# AugmentedStethoscope_v2c.net
KiCad netlist of a schematic drawn in EAGLE
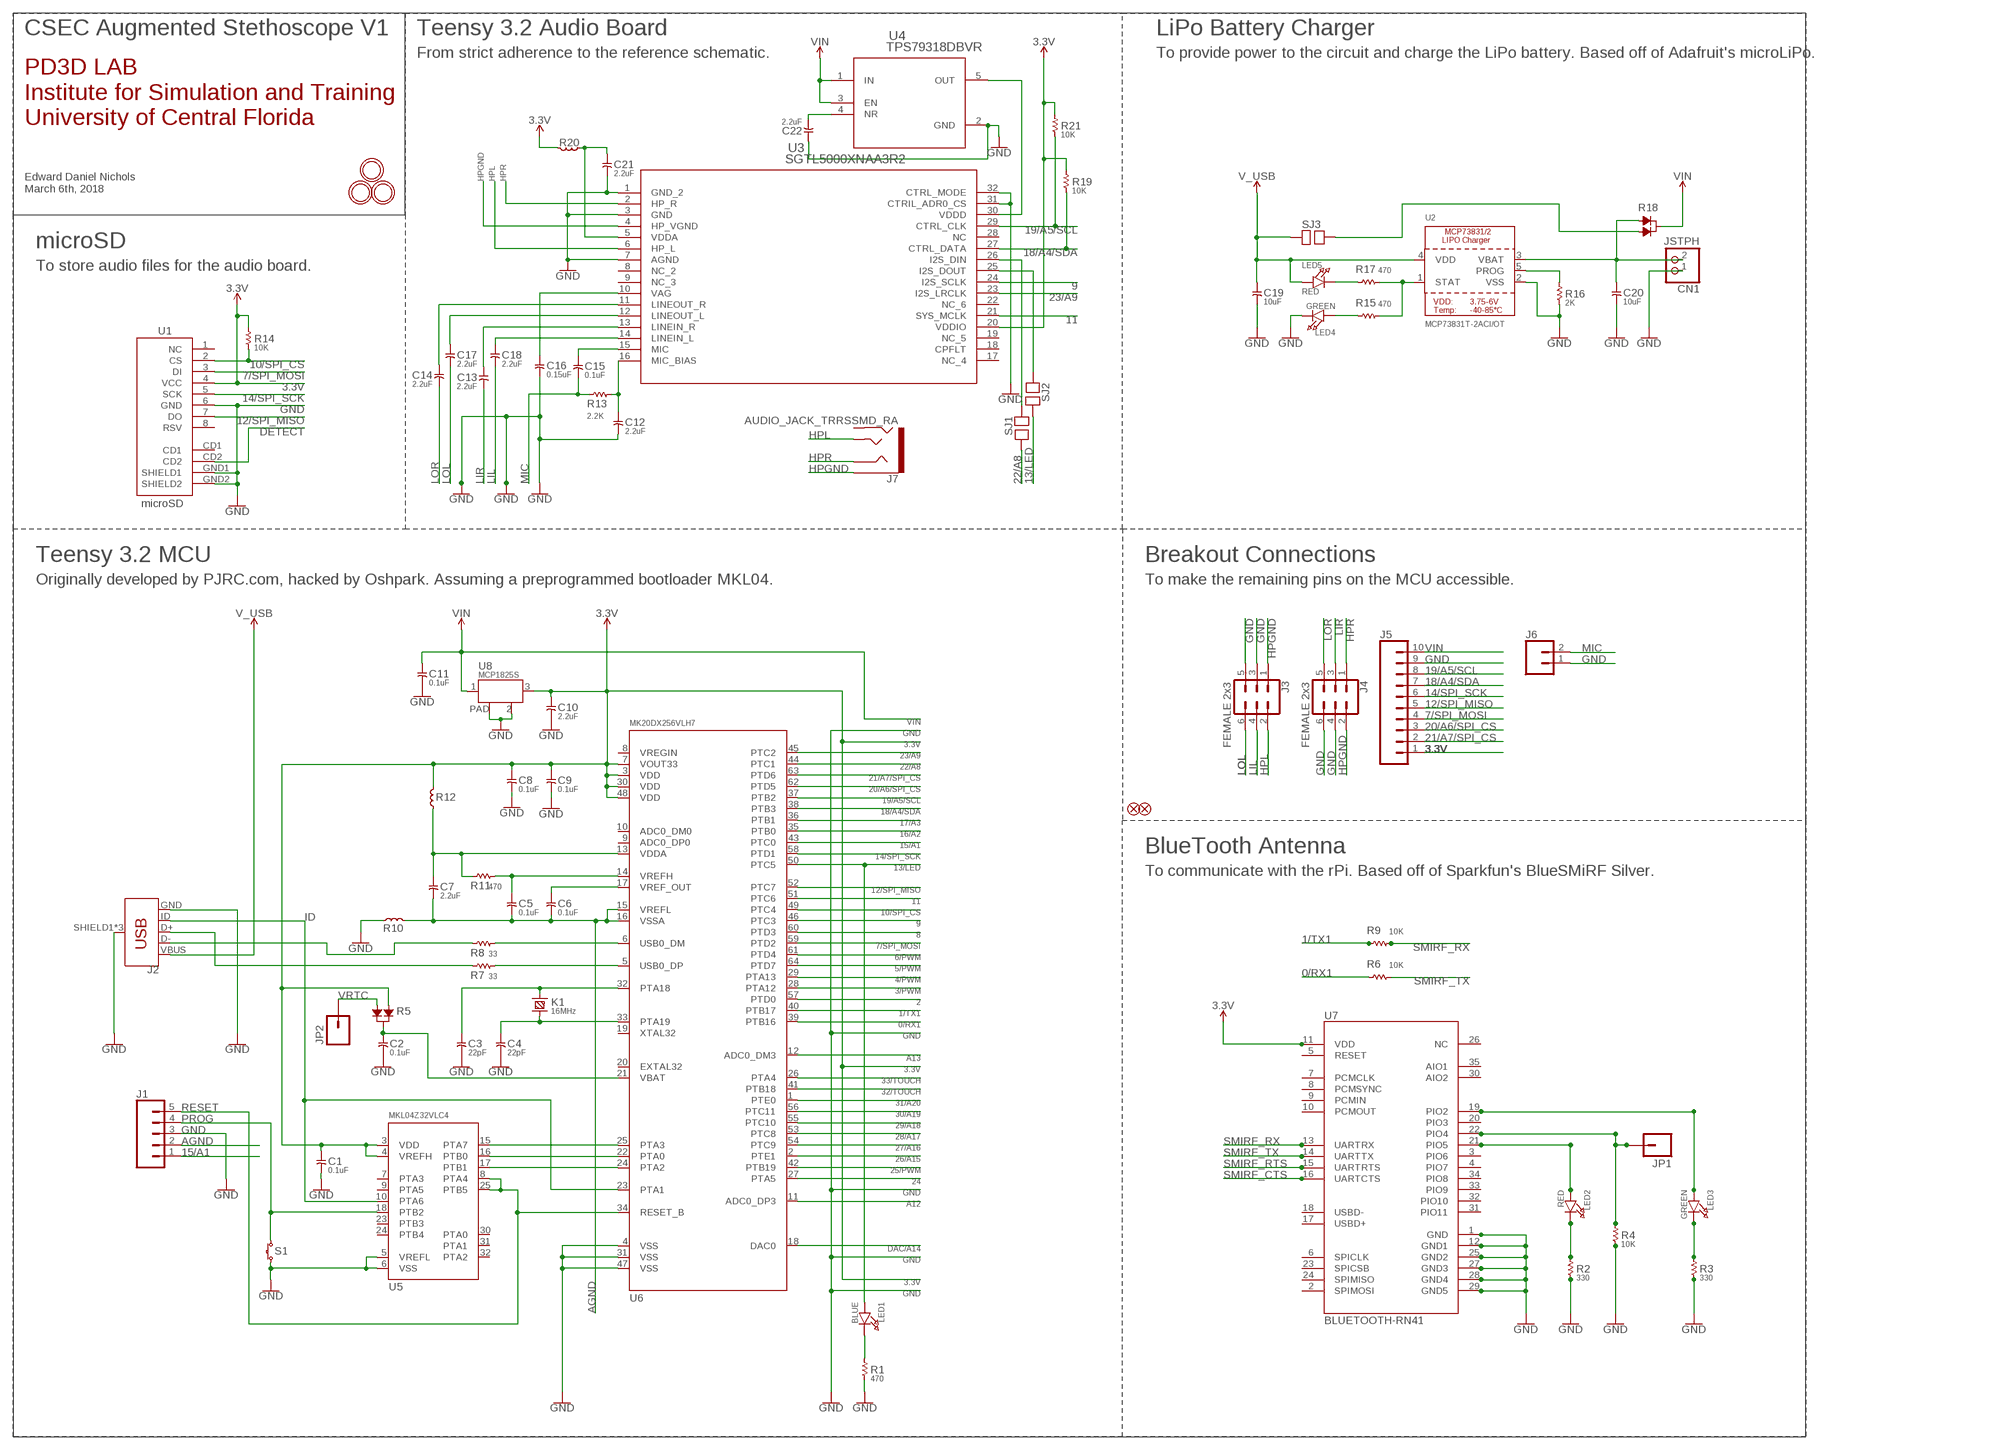
[diagram p0: schematic, sheet 1]

(export (version "E")
  (design (tool "Eeschema 10.0.6"))
  (components
    (comp (ref "C1")
      (value "0.1uF")
      (footprint "eagle-import:C0603")
      (fields (field (name "MF") "Murata Electronics") (field (name "MPN") "GRM188R71C104KA01D"))
      (libsource (lib "eagle-import") (part "CAPACITOR-0.1UF"))
    )
    (comp (ref "C2")
      (value "0.1uF")
      (footprint "eagle-import:C0603")
      (fields (field (name "MF") "Murata Electronics") (field (name "MPN") "GRM188R71C104KA01D"))
      (libsource (lib "eagle-import") (part "CAPACITOR-0.1UF"))
    )
    (comp (ref "C3")
      (value "22pF")
      (footprint "eagle-import:C0603")
      (fields (field (name "MF") "Vishay / Vitramon") (field (name "MPN") "VJ0603A220JXACW1BC"))
      (libsource (lib "eagle-import") (part "CAPACITOR-22PF"))
    )
    (comp (ref "C4")
      (value "22pF")
      (footprint "eagle-import:C0603")
      (fields (field (name "MF") "Vishay / Vitramon") (field (name "MPN") "VJ0603A220JXACW1BC"))
      (libsource (lib "eagle-import") (part "CAPACITOR-22PF"))
    )
    (comp (ref "C5")
      (value "0.1uF")
      (footprint "eagle-import:C0603")
      (fields (field (name "MF") "Murata Electronics") (field (name "MPN") "GRM188R71C104KA01D"))
      (libsource (lib "eagle-import") (part "CAPACITOR-0.1UF"))
    )
    (comp (ref "C6")
      (value "0.1uF")
      (footprint "eagle-import:C0603")
      (fields (field (name "MF") "Murata Electronics") (field (name "MPN") "GRM188R71C104KA01D"))
      (libsource (lib "eagle-import") (part "CAPACITOR-0.1UF"))
    )
    (comp (ref "C7")
      (value "2.2uF")
      (footprint "eagle-import:C0805")
      (fields (field (name "MF") "Taiyo Yuden") (field (name "MPN") "TMK212B7225KG-TR"))
      (libsource (lib "eagle-import") (part "CAPACITOR-2.2UF"))
    )
    (comp (ref "C8")
      (value "0.1uF")
      (footprint "eagle-import:C0603")
      (fields (field (name "MF") "Murata Electronics") (field (name "MPN") "GRM188R71C104KA01D"))
      (libsource (lib "eagle-import") (part "CAPACITOR-0.1UF"))
    )
    (comp (ref "C9")
      (value "0.1uF")
      (footprint "eagle-import:C0603")
      (fields (field (name "MF") "Murata Electronics") (field (name "MPN") "GRM188R71C104KA01D"))
      (libsource (lib "eagle-import") (part "CAPACITOR-0.1UF"))
    )
    (comp (ref "C10")
      (value "2.2uF")
      (footprint "eagle-import:C0805")
      (fields (field (name "MF") "Taiyo Yuden") (field (name "MPN") "TMK212B7225KG-TR"))
      (libsource (lib "eagle-import") (part "CAPACITOR-2.2UF"))
    )
    (comp (ref "C11")
      (value "0.1uF")
      (footprint "eagle-import:C0603")
      (fields (field (name "MF") "Murata Electronics") (field (name "MPN") "GRM188R71C104KA01D"))
      (libsource (lib "eagle-import") (part "CAPACITOR-0.1UF"))
    )
    (comp (ref "C12")
      (value "2.2uF")
      (footprint "eagle-import:C0805")
      (fields (field (name "MF") "Taiyo Yuden") (field (name "MPN") "TMK212B7225KG-TR"))
      (libsource (lib "eagle-import") (part "CAPACITOR-2.2UF"))
    )
    (comp (ref "C13")
      (value "2.2uF")
      (footprint "eagle-import:C0805")
      (fields (field (name "MF") "Taiyo Yuden") (field (name "MPN") "TMK212B7225KG-TR"))
      (libsource (lib "eagle-import") (part "CAPACITOR-2.2UF"))
    )
    (comp (ref "C14")
      (value "2.2uF")
      (footprint "eagle-import:C0805")
      (fields (field (name "MF") "Taiyo Yuden") (field (name "MPN") "TMK212B7225KG-TR"))
      (libsource (lib "eagle-import") (part "CAPACITOR-2.2UF"))
    )
    (comp (ref "C15")
      (value "0.1uF")
      (footprint "eagle-import:C0805")
      (fields (field (name "MF") "Taiyo Yuden") (field (name "MPN") "TMK212B7225KG-TR"))
      (libsource (lib "eagle-import") (part "CAPACITOR-2.2UF"))
    )
    (comp (ref "C16")
      (value "0.15uF")
      (footprint "eagle-import:C0603")
      (fields (field (name "MF") "Murata Electronics") (field (name "MPN") "GRM188R71C104KA01D"))
      (libsource (lib "eagle-import") (part "CAPACITOR-0.1UF"))
    )
    (comp (ref "C17")
      (value "2.2uF")
      (footprint "eagle-import:C0805")
      (fields (field (name "MF") "Taiyo Yuden") (field (name "MPN") "TMK212B7225KG-TR"))
      (libsource (lib "eagle-import") (part "CAPACITOR-2.2UF"))
    )
    (comp (ref "C18")
      (value "2.2uF")
      (footprint "eagle-import:C0805")
      (fields (field (name "MF") "Taiyo Yuden") (field (name "MPN") "TMK212B7225KG-TR"))
      (libsource (lib "eagle-import") (part "CAPACITOR-2.2UF"))
    )
    (comp (ref "C19")
      (value "10uF")
      (footprint "eagle-import:C0603")
      (fields (field (name "MF") "Murata Electronics") (field (name "MPN") "GRM188R71C104KA01D"))
      (libsource (lib "eagle-import") (part "CAPACITOR-0.1UF"))
    )
    (comp (ref "C20")
      (value "10uF")
      (footprint "eagle-import:C0603")
      (fields (field (name "MF") "Murata Electronics") (field (name "MPN") "GRM188R71C104KA01D"))
      (libsource (lib "eagle-import") (part "CAPACITOR-0.1UF"))
    )
    (comp (ref "C21")
      (value "2.2uF")
      (footprint "eagle-import:C0805")
      (fields (field (name "MF") "Taiyo Yuden") (field (name "MPN") "TMK212B7225KG-TR"))
      (libsource (lib "eagle-import") (part "CAPACITOR-2.2UF"))
    )
    (comp (ref "C22")
      (value "2.2uF")
      (footprint "eagle-import:C0805")
      (fields (field (name "MF") "Taiyo Yuden") (field (name "MPN") "TMK212B7225KG-TR"))
      (libsource (lib "eagle-import") (part "CAPACITOR-2.2UF"))
    )
    (comp (ref "CN1")
      (value "JSTPH")
      (footprint "eagle-import:JSTPH2")
      (libsource (lib "eagle-import") (part "JST_2PIN"))
    )
    (comp (ref "FID2")
      (value "FIDUCIAL\"\"")
      (footprint "eagle-import:FIDUCIAL_1MM")
      (libsource (lib "eagle-import") (part "FIDUCIAL{dblquote}{dblquote}"))
    )
    (comp (ref "FID3")
      (value "FIDUCIAL\"\"")
      (footprint "eagle-import:FIDUCIAL_1MM")
      (fields (field (name "BOM") "EXCLUDE"))
      (libsource (lib "eagle-import") (part "FIDUCIAL{dblquote}{dblquote}"))
    )
    (comp (ref "J1")
      (value "CONN_05")
      (footprint "eagle-import:1X05")
      (libsource (lib "eagle-import") (part "CONN_05"))
    )
    (comp (ref "J2")
      (value "USB_MICRO-B_FEMALE-SMT")
      (footprint "eagle-import:USB-B-MICRO-SMD")
      (libsource (lib "eagle-import") (part "USB_MICRO-B_FEMALE-SMT"))
    )
    (comp (ref "J3")
      (value "FEMALE 2x3")
      (footprint "eagle-import:2X3")
      (libsource (lib "eagle-import") (part "CONN_03X2FEMALE"))
    )
    (comp (ref "J4")
      (value "FEMALE 2x3")
      (footprint "eagle-import:2X3")
      (libsource (lib "eagle-import") (part "CONN_03X2FEMALE"))
    )
    (comp (ref "J5")
      (value "CONN_10\"")
      (footprint "eagle-import:1X10")
      (libsource (lib "eagle-import") (part "CONN_10{dblquote}"))
    )
    (comp (ref "J6")
      (value "CONN_02")
      (footprint "eagle-import:1X02")
      (libsource (lib "eagle-import") (part "CONN_02"))
    )
    (comp (ref "J7")
      (value "AUDIO_JACK_TRRSSMD_RA")
      (footprint "eagle-import:AUDIO_JACK_3.5MM_TRRS_SMD_RA")
      (libsource (lib "eagle-import") (part "AUDIO_JACK_TRRSSMD_RA"))
    )
    (comp (ref "JP1")
      (value "M01SMDNS")
      (footprint "eagle-import:1X01NS")
      (libsource (lib "eagle-import") (part "M01SMDNS"))
    )
    (comp (ref "JP2")
      (value "M01SMDNS")
      (footprint "eagle-import:1X01NS")
      (libsource (lib "eagle-import") (part "M01SMDNS"))
    )
    (comp (ref "K1")
      (value "16MHz")
      (footprint "eagle-import:HC49US")
      (fields (field (name "MF") "ABRACON") (field (name "MPN") "ABL-16.000MHz-B1U"))
      (libsource (lib "eagle-import") (part "CRYSTAL-HC49US"))
    )
    (comp (ref "LED1")
      (value "BLUE")
      (footprint "eagle-import:CHIPLED_0805")
      (libsource (lib "eagle-import") (part "LED0805"))
    )
    (comp (ref "LED2")
      (value "RED")
      (footprint "eagle-import:CHIPLED_0805")
      (libsource (lib "eagle-import") (part "LED0805"))
    )
    (comp (ref "LED3")
      (value "GREEN")
      (footprint "eagle-import:CHIPLED_0805")
      (libsource (lib "eagle-import") (part "LED0805"))
    )
    (comp (ref "LED4")
      (value "GREEN")
      (footprint "eagle-import:CHIPLED_0805")
      (libsource (lib "eagle-import") (part "LED0805"))
    )
    (comp (ref "LED5")
      (value "RED")
      (footprint "eagle-import:CHIPLED_0805")
      (libsource (lib "eagle-import") (part "LED0805"))
    )
    (comp (ref "R1")
      (value "470")
      (footprint "eagle-import:R0603")
      (fields (field (name "MF") "Vishay") (field (name "MPN") "CRCW0603470RFKEA"))
      (libsource (lib "eagle-import") (part "RESISTOR-470R"))
    )
    (comp (ref "R2")
      (value "330")
      (footprint "eagle-import:R0603")
      (fields (field (name "MF") "Vishay") (field (name "MPN") "CRCW0603470RFKEA"))
      (libsource (lib "eagle-import") (part "RESISTOR-470R"))
    )
    (comp (ref "R3")
      (value "330")
      (footprint "eagle-import:R0603")
      (fields (field (name "MF") "Vishay") (field (name "MPN") "CRCW0603470RFKEA"))
      (libsource (lib "eagle-import") (part "RESISTOR-470R"))
    )
    (comp (ref "R4")
      (value "10K")
      (footprint "eagle-import:R0603")
      (fields (field (name "MF") "Vishay") (field (name "MPN") "CRCW0603470RFKEA"))
      (libsource (lib "eagle-import") (part "RESISTOR-470R"))
    )
    (comp (ref "R5")
      (value "DIODE_DUAL")
      (footprint "eagle-import:SOT-23")
      (fields (field (name "MF") "NXP Semiconductors") (field (name "MPN") "BAT54C,215"))
      (libsource (lib "eagle-import") (part "DIODE_DUAL"))
    )
    (comp (ref "R6")
      (value "10K")
      (footprint "eagle-import:R0603")
      (fields (field (name "MF") "Panasonic") (field (name "MPN") "ERJ-PA3F33R0V"))
      (libsource (lib "eagle-import") (part "RESISTOR-33R"))
    )
    (comp (ref "R7")
      (value "33")
      (footprint "eagle-import:R0603")
      (fields (field (name "MF") "Panasonic") (field (name "MPN") "ERJ-PA3F33R0V"))
      (libsource (lib "eagle-import") (part "RESISTOR-33R"))
    )
    (comp (ref "R8")
      (value "33")
      (footprint "eagle-import:R0603")
      (fields (field (name "MF") "Panasonic") (field (name "MPN") "ERJ-PA3F33R0V"))
      (libsource (lib "eagle-import") (part "RESISTOR-33R"))
    )
    (comp (ref "R9")
      (value "10K")
      (footprint "eagle-import:R0603")
      (fields (field (name "MF") "Panasonic") (field (name "MPN") "ERJ-PA3F33R0V"))
      (libsource (lib "eagle-import") (part "RESISTOR-33R"))
    )
    (comp (ref "R10")
      (value "FERRITE")
      (footprint "eagle-import:L0603")
      (fields (field (name "MF") "Murata Electronics") (field (name "MPN") " BLM18AG601SN1D"))
      (libsource (lib "eagle-import") (part "FERRITE"))
    )
    (comp (ref "R11")
      (value "470")
      (footprint "eagle-import:R0603")
      (fields (field (name "MF") "Vishay") (field (name "MPN") "CRCW0603470RFKEA"))
      (libsource (lib "eagle-import") (part "RESISTOR-470R"))
    )
    (comp (ref "R12")
      (value "FERRITE")
      (footprint "eagle-import:L0603")
      (fields (field (name "MF") "Murata Electronics") (field (name "MPN") " BLM18AG601SN1D"))
      (libsource (lib "eagle-import") (part "FERRITE"))
    )
    (comp (ref "R13")
      (value "2.2K")
      (footprint "eagle-import:R0603")
      (fields (field (name "MF") "Vishay") (field (name "MPN") "CRCW0603470RFKEA"))
      (libsource (lib "eagle-import") (part "RESISTOR-470R"))
    )
    (comp (ref "R14")
      (value "10K")
      (footprint "eagle-import:R0603")
      (fields (field (name "MF") "Vishay") (field (name "MPN") "CRCW0603470RFKEA"))
      (libsource (lib "eagle-import") (part "RESISTOR-470R"))
    )
    (comp (ref "R15")
      (value "470")
      (footprint "eagle-import:R0603")
      (fields (field (name "MF") "Panasonic") (field (name "MPN") "ERJ-PA3F33R0V"))
      (libsource (lib "eagle-import") (part "RESISTOR-33R"))
    )
    (comp (ref "R16")
      (value "2K")
      (footprint "eagle-import:R0603")
      (fields (field (name "MF") "Vishay") (field (name "MPN") "CRCW0603470RFKEA"))
      (libsource (lib "eagle-import") (part "RESISTOR-470R"))
    )
    (comp (ref "R17")
      (value "470")
      (footprint "eagle-import:R0603")
      (fields (field (name "MF") "Panasonic") (field (name "MPN") "ERJ-PA3F33R0V"))
      (libsource (lib "eagle-import") (part "RESISTOR-33R"))
    )
    (comp (ref "R18")
      (value "DIODE_DUAL")
      (footprint "eagle-import:SOT-23")
      (fields (field (name "MF") "NXP Semiconductors") (field (name "MPN") "BAT54C,215"))
      (libsource (lib "eagle-import") (part "DIODE_DUAL"))
    )
    (comp (ref "R19")
      (value "10K")
      (footprint "eagle-import:R0603")
      (fields (field (name "MF") "Vishay") (field (name "MPN") "CRCW0603470RFKEA"))
      (libsource (lib "eagle-import") (part "RESISTOR-470R"))
    )
    (comp (ref "R20")
      (value "FERRITE")
      (footprint "eagle-import:L0603")
      (fields (field (name "MF") "Murata Electronics") (field (name "MPN") " BLM18AG601SN1D"))
      (libsource (lib "eagle-import") (part "FERRITE"))
    )
    (comp (ref "R21")
      (value "10K")
      (footprint "eagle-import:R0603")
      (fields (field (name "MF") "Vishay") (field (name "MPN") "CRCW0603470RFKEA"))
      (libsource (lib "eagle-import") (part "RESISTOR-470R"))
    )
    (comp (ref "S1")
      (value "TACT_SWITCH")
      (footprint "eagle-import:ALPS_SKHH")
      (fields (field (name "MF") "ALPS") (field (name "MPN") "SKHHPKA010"))
      (libsource (lib "eagle-import") (part "TACT_SWITCH"))
    )
    (comp (ref "SJ1")
      (value "SOLDERJUMPER")
      (footprint "eagle-import:SOLDERJUMPER")
      (libsource (lib "eagle-import") (part "SOLDERJUMPER"))
    )
    (comp (ref "SJ2")
      (value "SOLDERJUMPER")
      (footprint "eagle-import:SOLDERJUMPER")
      (libsource (lib "eagle-import") (part "SOLDERJUMPER"))
    )
    (comp (ref "SJ3")
      (value "SOLDERJUMPER")
      (footprint "eagle-import:SOLDERJUMPER")
      (libsource (lib "eagle-import") (part "SOLDERJUMPER"))
    )
    (comp (ref "U$1")
      (value "MOUNTINGHOLE2.5")
      (footprint "eagle-import:MOUNTINGHOLE_2.5_PLATED")
      (libsource (lib "eagle-import") (part "MOUNTINGHOLE2.5"))
    )
    (comp (ref "U$3")
      (value "MOUNTINGHOLE2.5")
      (footprint "eagle-import:MOUNTINGHOLE_2.5_PLATED")
      (libsource (lib "eagle-import") (part "MOUNTINGHOLE2.5"))
    )
    (comp (ref "U$15")
      (value "MOUNTINGHOLE2.5")
      (footprint "eagle-import:MOUNTINGHOLE_2.5_PLATED")
      (libsource (lib "eagle-import") (part "MOUNTINGHOLE2.5"))
    )
    (comp (ref "U1")
      (value "microSD")
      (footprint "eagle-import:MICRO-SD-SOCKET-PP")
      (libsource (lib "eagle-import") (part "USD-SOCKETSMD"))
    )
    (comp (ref "U2")
      (value "MCP73831T-2ACI/OT")
      (footprint "eagle-import:SOT23-5")
      (libsource (lib "eagle-import") (part "MCP73831/2"))
    )
    (comp (ref "U3")
      (value "SGTL5000XNAA3R2")
      (footprint "eagle-import:QFN32")
      (libsource (lib "eagle-import") (part "SGTL5000XNAA3R2"))
    )
    (comp (ref "U4")
      (value "TPS79318DBVR")
      (footprint "eagle-import:DBV5")
      (libsource (lib "eagle-import") (part "TPS79318DBVR"))
    )
    (comp (ref "U5")
      (value "MKL04Z32VLC4")
      (footprint "eagle-import:LQFP32-08")
      (fields (field (name "MF") "PJRC") (field (name "MPN") "IC_MKL04Z32_TQFP32"))
      (libsource (lib "eagle-import") (part "MKL04Z32VLC4"))
    )
    (comp (ref "U6")
      (value "MK20DX256VLH7")
      (footprint "eagle-import:LQFP64-05")
      (fields (field (name "MF") "NXP"))
      (libsource (lib "eagle-import") (part "MK20DX256VLH7"))
    )
    (comp (ref "U7")
      (value "BLUETOOTH-RN41")
      (footprint "eagle-import:RN41")
      (libsource (lib "eagle-import") (part "BLUETOOTH-RN41{dblquote}"))
    )
    (comp (ref "U8")
      (value "MCP1825S")
      (footprint "eagle-import:SOT-223")
      (fields (field (name "MF") "Microchip Technology") (field (name "MPN") "MCP1825S-3302E/DB"))
      (libsource (lib "eagle-import") (part "LDO"))
    )
  )
  (nets
    (net (code "1") (name "/0{slash}RX1") (class "Default")
      (node (ref "R6") (pin "1") (pinfunction "1_1") (pintype "passive"))
      (node (ref "U6") (pin "39") (pinfunction "PTB16_39") (pintype "bidirectional"))
    )
    (net (code "2") (name "/1{slash}TX1") (class "Default")
      (node (ref "R9") (pin "1") (pinfunction "1_1") (pintype "passive"))
      (node (ref "U6") (pin "40") (pinfunction "PTB17_40") (pintype "bidirectional"))
    )
    (net (code "3") (name "/2") (class "Default")
      (node (ref "U6") (pin "57") (pinfunction "PTD0_57") (pintype "bidirectional"))
    )
    (net (code "4") (name "/3{slash}PWM") (class "Default")
      (node (ref "U6") (pin "28") (pinfunction "PTA12_28") (pintype "bidirectional"))
    )
    (net (code "5") (name "/4{slash}PWM") (class "Default")
      (node (ref "U6") (pin "29") (pinfunction "PTA13_29") (pintype "bidirectional"))
    )
    (net (code "6") (name "/5{slash}PWM") (class "Default")
      (node (ref "U6") (pin "64") (pinfunction "PTD7_64") (pintype "bidirectional"))
    )
    (net (code "7") (name "/6{slash}PWM") (class "Default")
      (node (ref "U6") (pin "61") (pinfunction "PTD4_61") (pintype "bidirectional"))
    )
    (net (code "8") (name "/7{slash}SPI_MOSI") (class "Default")
      (node (ref "J5") (pin "4") (pinfunction "4_4") (pintype "passive"))
      (node (ref "U1") (pin "3") (pinfunction "DI_3") (pintype "bidirectional"))
      (node (ref "U6") (pin "59") (pinfunction "PTD2_59") (pintype "bidirectional"))
    )
    (net (code "9") (name "/8") (class "Default")
      (node (ref "U6") (pin "60") (pinfunction "PTD3_60") (pintype "bidirectional"))
    )
    (net (code "10") (name "/9") (class "Default")
      (node (ref "U3") (pin "24") (pinfunction "I2S_SCLK_24") (pintype "passive"))
      (node (ref "U6") (pin "46") (pinfunction "PTC3_46") (pintype "bidirectional"))
    )
    (net (code "11") (name "/10{slash}SPI_CS") (class "Default")
      (node (ref "R14") (pin "1") (pinfunction "1_1") (pintype "passive"))
      (node (ref "U1") (pin "2") (pinfunction "CS_2") (pintype "bidirectional"))
      (node (ref "U6") (pin "49") (pinfunction "PTC4_49") (pintype "bidirectional"))
    )
    (net (code "12") (name "/11") (class "Default")
      (node (ref "U3") (pin "21") (pinfunction "SYS_MCLK_21") (pintype "passive"))
      (node (ref "U6") (pin "51") (pinfunction "PTC6_51") (pintype "bidirectional"))
    )
    (net (code "13") (name "/12{slash}SPI_MISO") (class "Default")
      (node (ref "J5") (pin "5") (pinfunction "5_5") (pintype "passive"))
      (node (ref "U1") (pin "7") (pinfunction "DO_7") (pintype "bidirectional"))
      (node (ref "U6") (pin "52") (pinfunction "PTC7_52") (pintype "bidirectional"))
    )
    (net (code "14") (name "/13{slash}LED") (class "Default")
      (node (ref "LED1") (pin "A") (pinfunction "A_A") (pintype "passive"))
      (node (ref "SJ2") (pin "2") (pinfunction "2_2") (pintype "passive"))
      (node (ref "U6") (pin "50") (pinfunction "PTC5_50") (pintype "bidirectional"))
    )
    (net (code "15") (name "/14{slash}SPI_SCK") (class "Default")
      (node (ref "J5") (pin "6") (pinfunction "6_6") (pintype "passive"))
      (node (ref "U1") (pin "5") (pinfunction "SCK_5") (pintype "bidirectional"))
      (node (ref "U6") (pin "58") (pinfunction "PTD1_58") (pintype "bidirectional"))
    )
    (net (code "16") (name "/15{slash}A1") (class "Default")
      (node (ref "J1") (pin "1") (pinfunction "1_1") (pintype "passive"))
      (node (ref "U6") (pin "43") (pinfunction "PTC0_43") (pintype "bidirectional"))
    )
    (net (code "17") (name "/16{slash}A2") (class "Default")
      (node (ref "U6") (pin "35") (pinfunction "PTB0_35") (pintype "bidirectional"))
    )
    (net (code "18") (name "/17{slash}A3") (class "Default")
      (node (ref "U6") (pin "36") (pinfunction "PTB1_36") (pintype "bidirectional"))
    )
    (net (code "19") (name "/18{slash}A4{slash}SDA") (class "Default")
      (node (ref "J5") (pin "7") (pinfunction "7_7") (pintype "passive"))
      (node (ref "R19") (pin "1") (pinfunction "1_1") (pintype "passive"))
      (node (ref "U3") (pin "27") (pinfunction "CTRL_DATA_27") (pintype "passive"))
      (node (ref "U6") (pin "38") (pinfunction "PTB3_38") (pintype "bidirectional"))
    )
    (net (code "20") (name "/19{slash}A5{slash}SCL") (class "Default")
      (node (ref "J5") (pin "8") (pinfunction "8_8") (pintype "passive"))
      (node (ref "R21") (pin "1") (pinfunction "1_1") (pintype "passive"))
      (node (ref "U3") (pin "29") (pinfunction "CTRL_CLK_29") (pintype "passive"))
      (node (ref "U6") (pin "37") (pinfunction "PTB2_37") (pintype "bidirectional"))
    )
    (net (code "21") (name "/20{slash}A6{slash}SPI_CS") (class "Default")
      (node (ref "J5") (pin "3") (pinfunction "3_3") (pintype "passive"))
      (node (ref "U6") (pin "62") (pinfunction "PTD5_62") (pintype "bidirectional"))
    )
    (net (code "22") (name "/21{slash}A7{slash}SPI_CS") (class "Default")
      (node (ref "J5") (pin "2") (pinfunction "2_2") (pintype "passive"))
      (node (ref "U6") (pin "63") (pinfunction "PTD6_63") (pintype "bidirectional"))
    )
    (net (code "23") (name "/22{slash}A8") (class "Default")
      (node (ref "SJ1") (pin "2") (pinfunction "2_2") (pintype "passive"))
      (node (ref "U6") (pin "44") (pinfunction "PTC1_44") (pintype "bidirectional"))
    )
    (net (code "24") (name "/23{slash}A9") (class "Default")
      (node (ref "U3") (pin "23") (pinfunction "I2S_LRCLK_23") (pintype "passive"))
      (node (ref "U6") (pin "45") (pinfunction "PTC2_45") (pintype "bidirectional"))
    )
    (net (code "25") (name "/24") (class "Default")
      (node (ref "U6") (pin "27") (pinfunction "PTA5_27") (pintype "bidirectional"))
    )
    (net (code "26") (name "/25{slash}PWM") (class "Default")
      (node (ref "U6") (pin "42") (pinfunction "PTB19_42") (pintype "bidirectional"))
    )
    (net (code "27") (name "/26{slash}A15") (class "Default")
      (node (ref "U6") (pin "2") (pinfunction "PTE1_2") (pintype "bidirectional"))
    )
    (net (code "28") (name "/27{slash}A16") (class "Default")
      (node (ref "U6") (pin "54") (pinfunction "PTC9_54") (pintype "bidirectional"))
    )
    (net (code "29") (name "/28{slash}A17") (class "Default")
      (node (ref "U6") (pin "53") (pinfunction "PTC8_53") (pintype "bidirectional"))
    )
    (net (code "30") (name "/29{slash}A18") (class "Default")
      (node (ref "U6") (pin "55") (pinfunction "PTC10_55") (pintype "bidirectional"))
    )
    (net (code "31") (name "/30{slash}A19") (class "Default")
      (node (ref "U6") (pin "56") (pinfunction "PTC11_56") (pintype "bidirectional"))
    )
    (net (code "32") (name "/31{slash}A20") (class "Default")
      (node (ref "U6") (pin "1") (pinfunction "PTE0_1") (pintype "bidirectional"))
    )
    (net (code "33") (name "/32{slash}TOUCH") (class "Default")
      (node (ref "U6") (pin "41") (pinfunction "PTB18_41") (pintype "bidirectional"))
    )
    (net (code "34") (name "/33{slash}TOUCH") (class "Default")
      (node (ref "U6") (pin "26") (pinfunction "PTA4_26") (pintype "bidirectional"))
    )
    (net (code "35") (name "/A12") (class "Default")
      (node (ref "U6") (pin "11") (pinfunction "ADC0_DP3_11") (pintype "bidirectional"))
    )
    (net (code "36") (name "/A13") (class "Default")
      (node (ref "U6") (pin "12") (pinfunction "ADC0_DM3_12") (pintype "bidirectional"))
    )
    (net (code "37") (name "/AGND") (class "Default")
      (node (ref "C5") (pin "2") (pinfunction "2_2") (pintype "passive"))
      (node (ref "C6") (pin "2") (pinfunction "2_2") (pintype "passive"))
      (node (ref "C7") (pin "2") (pinfunction "2_2") (pintype "passive"))
      (node (ref "J1") (pin "2") (pinfunction "2_2") (pintype "passive"))
      (node (ref "R10") (pin "2") (pinfunction "2_2") (pintype "passive"))
      (node (ref "U6") (pin "15") (pinfunction "VREFL_15") (pintype "bidirectional"))
      (node (ref "U6") (pin "16") (pinfunction "VSSA_16") (pintype "bidirectional"))
    )
    (net (code "38") (name "/DAC{slash}A14") (class "Default")
      (node (ref "U6") (pin "18") (pinfunction "DAC0_18") (pintype "bidirectional"))
    )
    (net (code "39") (name "/DETECT") (class "Default")
      (node (ref "U1") (pin "CD2") (pinfunction "CD2_CD2") (pintype "bidirectional"))
    )
    (net (code "40") (name "/HPGND") (class "Default")
      (node (ref "J3") (pin "1") (pinfunction "1_1") (pintype "bidirectional"))
      (node (ref "J4") (pin "2") (pinfunction "2_2") (pintype "bidirectional"))
      (node (ref "J7") (pin "EARTH") (pinfunction "EARTH_EARTH") (pintype "bidirectional"))
      (node (ref "U3") (pin "4") (pinfunction "HP_VGND_4") (pintype "power_in"))
    )
    (net (code "41") (name "/HPL") (class "Default")
      (node (ref "J3") (pin "2") (pinfunction "2_2") (pintype "bidirectional"))
      (node (ref "J7") (pin "TIP") (pinfunction "TIP_TIP") (pintype "bidirectional"))
      (node (ref "U3") (pin "6") (pinfunction "HP_L_6") (pintype "output"))
    )
    (net (code "42") (name "/HPR") (class "Default")
      (node (ref "J4") (pin "1") (pinfunction "1_1") (pintype "bidirectional"))
      (node (ref "J7") (pin "RING1") (pinfunction "RING1_RING1") (pintype "bidirectional"))
      (node (ref "U3") (pin "2") (pinfunction "HP_R_2") (pintype "output"))
    )
    (net (code "43") (name "/ID") (class "Default")
      (node (ref "J2") (pin "ID") (pinfunction "ID_ID") (pintype "bidirectional"))
      (node (ref "U5") (pin "10") (pinfunction "PTA6_10") (pintype "bidirectional"))
      (node (ref "U6") (pin "23") (pinfunction "PTA1_23") (pintype "bidirectional"))
    )
    (net (code "44") (name "/LIL") (class "Default")
      (node (ref "C18") (pin "2") (pinfunction "2_2") (pintype "passive"))
      (node (ref "J3") (pin "4") (pinfunction "4_4") (pintype "bidirectional"))
    )
    (net (code "45") (name "/LIR") (class "Default")
      (node (ref "C13") (pin "2") (pinfunction "2_2") (pintype "passive"))
      (node (ref "J4") (pin "3") (pinfunction "3_3") (pintype "bidirectional"))
    )
    (net (code "46") (name "/LOL") (class "Default")
      (node (ref "C17") (pin "2") (pinfunction "2_2") (pintype "passive"))
      (node (ref "J3") (pin "6") (pinfunction "6_6") (pintype "bidirectional"))
    )
    (net (code "47") (name "/LOR") (class "Default")
      (node (ref "C14") (pin "2") (pinfunction "2_2") (pintype "passive"))
      (node (ref "J4") (pin "5") (pinfunction "5_5") (pintype "bidirectional"))
    )
    (net (code "48") (name "/MIC") (class "Default")
      (node (ref "C15") (pin "2") (pinfunction "2_2") (pintype "passive"))
      (node (ref "J6") (pin "2") (pinfunction "2_2") (pintype "passive"))
      (node (ref "R13") (pin "1") (pinfunction "1_1") (pintype "passive"))
    )
    (net (code "49") (name "/PROG") (class "Default")
      (node (ref "J1") (pin "4") (pinfunction "4_4") (pintype "passive"))
      (node (ref "S1") (pin "1") (pinfunction "1_1") (pintype "passive"))
      (node (ref "S1") (pin "2") (pinfunction "1_2") (pintype "passive"))
      (node (ref "U5") (pin "18") (pinfunction "PTB2_18") (pintype "bidirectional"))
    )
    (net (code "50") (name "/RESET") (class "Default")
      (node (ref "J1") (pin "5") (pinfunction "5_5") (pintype "passive"))
      (node (ref "U5") (pin "25") (pinfunction "PTB5_25") (pintype "bidirectional"))
      (node (ref "U5") (pin "8") (pinfunction "PTA4_8") (pintype "bidirectional"))
      (node (ref "U6") (pin "34") (pinfunction "RESET_B_34") (pintype "bidirectional"))
    )
    (net (code "51") (name "/SMIRF_CTS") (class "Default")
      (node (ref "U7") (pin "16") (pinfunction "UARTCTS_16") (pintype "bidirectional"))
    )
    (net (code "52") (name "/SMIRF_RTS") (class "Default")
      (node (ref "U7") (pin "15") (pinfunction "UARTRTS_15") (pintype "bidirectional"))
    )
    (net (code "53") (name "/SMIRF_RX") (class "Default")
      (node (ref "R9") (pin "2") (pinfunction "2_2") (pintype "passive"))
      (node (ref "U7") (pin "13") (pinfunction "UARTRX_13") (pintype "bidirectional"))
    )
    (net (code "54") (name "/SMIRF_TX") (class "Default")
      (node (ref "R6") (pin "2") (pinfunction "2_2") (pintype "passive"))
      (node (ref "U7") (pin "14") (pinfunction "UARTTX_14") (pintype "bidirectional"))
    )
    (net (code "55") (name "/VRTC") (class "Default")
      (node (ref "JP2") (pin "1") (pinfunction "1_1") (pintype "passive"))
      (node (ref "R5") (pin "2") (pinfunction "2_2") (pintype "bidirectional"))
    )
    (net (code "56") (name "3.3V") (class "Default")
      (node (ref "C1") (pin "1") (pinfunction "1_1") (pintype "passive"))
      (node (ref "C10") (pin "1") (pinfunction "1_1") (pintype "passive"))
      (node (ref "C8") (pin "1") (pinfunction "1_1") (pintype "passive"))
      (node (ref "C9") (pin "1") (pinfunction "1_1") (pintype "passive"))
      (node (ref "J5") (pin "1") (pinfunction "1_1") (pintype "passive"))
      (node (ref "R12") (pin "2") (pinfunction "2_2") (pintype "passive"))
      (node (ref "R14") (pin "2") (pinfunction "2_2") (pintype "passive"))
      (node (ref "R19") (pin "2") (pinfunction "2_2") (pintype "passive"))
      (node (ref "R20") (pin "2") (pinfunction "2_2") (pintype "passive"))
      (node (ref "R21") (pin "2") (pinfunction "2_2") (pintype "passive"))
      (node (ref "R5") (pin "1") (pinfunction "1_1") (pintype "bidirectional"))
      (node (ref "U1") (pin "4") (pinfunction "VCC_4") (pintype "bidirectional"))
      (node (ref "U3") (pin "20") (pinfunction "VDDIO_20") (pintype "power_in"))
      (node (ref "U5") (pin "3") (pinfunction "VDD_3") (pintype "bidirectional"))
      (node (ref "U5") (pin "4") (pinfunction "VREFH_4") (pintype "bidirectional"))
      (node (ref "U6") (pin "3") (pinfunction "VDD_3") (pintype "bidirectional"))
      (node (ref "U6") (pin "30") (pinfunction "VDD_30") (pintype "bidirectional"))
      (node (ref "U6") (pin "48") (pinfunction "VDD_48") (pintype "bidirectional"))
      (node (ref "U6") (pin "7") (pinfunction "VOUT33_7") (pintype "bidirectional"))
      (node (ref "U7") (pin "11") (pinfunction "VDD_11") (pintype "bidirectional"))
      (node (ref "U8") (pin "3") (pinfunction "OUT_3") (pintype "bidirectional"))
    )
    (net (code "57") (name "GND") (class "Default")
      (node (ref "C1") (pin "2") (pinfunction "2_2") (pintype "passive"))
      (node (ref "C10") (pin "2") (pinfunction "2_2") (pintype "passive"))
      (node (ref "C11") (pin "2") (pinfunction "2_2") (pintype "passive"))
      (node (ref "C12") (pin "2") (pinfunction "2_2") (pintype "passive"))
      (node (ref "C16") (pin "2") (pinfunction "2_2") (pintype "passive"))
      (node (ref "C19") (pin "2") (pinfunction "2_2") (pintype "passive"))
      (node (ref "C2") (pin "2") (pinfunction "2_2") (pintype "passive"))
      (node (ref "C20") (pin "2") (pinfunction "2_2") (pintype "passive"))
      (node (ref "C21") (pin "2") (pinfunction "2_2") (pintype "passive"))
      (node (ref "C22") (pin "1") (pinfunction "1_1") (pintype "passive"))
      (node (ref "C3") (pin "2") (pinfunction "2_2") (pintype "passive"))
      (node (ref "C4") (pin "2") (pinfunction "2_2") (pintype "passive"))
      (node (ref "C8") (pin "2") (pinfunction "2_2") (pintype "passive"))
      (node (ref "C9") (pin "2") (pinfunction "2_2") (pintype "passive"))
      (node (ref "CN1") (pin "1") (pinfunction "1_1") (pintype "passive"))
      (node (ref "J1") (pin "3") (pinfunction "3_3") (pintype "passive"))
      (node (ref "J2") (pin "GND") (pinfunction "GND_GND") (pintype "power_in"))
      (node (ref "J2") (pin "SHIELD1") (pinfunction "SHIELD_SHIELD1") (pintype "bidirectional"))
      (node (ref "J2") (pin "SHIELD2") (pinfunction "SHIELD_SHIELD2") (pintype "bidirectional"))
      (node (ref "J2") (pin "SHIELD3") (pinfunction "SHIELD_SHIELD3") (pintype "bidirectional"))
      (node (ref "J3") (pin "3") (pinfunction "3_3") (pintype "bidirectional"))
      (node (ref "J3") (pin "5") (pinfunction "5_5") (pintype "bidirectional"))
      (node (ref "J4") (pin "4") (pinfunction "4_4") (pintype "bidirectional"))
      (node (ref "J4") (pin "6") (pinfunction "6_6") (pintype "bidirectional"))
      (node (ref "J5") (pin "9") (pinfunction "9_9") (pintype "passive"))
      (node (ref "J6") (pin "1") (pinfunction "1_1") (pintype "passive"))
      (node (ref "LED4") (pin "C") (pinfunction "C_C") (pintype "passive"))
      (node (ref "R1") (pin "1") (pinfunction "1_1") (pintype "passive"))
      (node (ref "R10") (pin "1") (pinfunction "1_1") (pintype "passive"))
      (node (ref "R16") (pin "1") (pinfunction "1_1") (pintype "passive"))
      (node (ref "R2") (pin "1") (pinfunction "1_1") (pintype "passive"))
      (node (ref "R3") (pin "1") (pinfunction "1_1") (pintype "passive"))
      (node (ref "R4") (pin "1") (pinfunction "1_1") (pintype "passive"))
      (node (ref "S1") (pin "3") (pinfunction "3_3") (pintype "passive"))
      (node (ref "S1") (pin "4") (pinfunction "3_4") (pintype "passive"))
      (node (ref "U1") (pin "6") (pinfunction "GND_6") (pintype "bidirectional"))
      (node (ref "U1") (pin "GND1") (pinfunction "SHIELD1_GND1") (pintype "bidirectional"))
      (node (ref "U1") (pin "GND2") (pinfunction "SHIELD2_GND2") (pintype "bidirectional"))
      (node (ref "U2") (pin "2") (pinfunction "VSS_2") (pintype "power_in"))
      (node (ref "U3") (pin "1") (pinfunction "GND_2_1") (pintype "power_in"))
      (node (ref "U3") (pin "3") (pinfunction "GND_3") (pintype "power_in"))
      (node (ref "U3") (pin "31") (pinfunction "CTRIL_ADR0_CS_31") (pintype "passive"))
      (node (ref "U3") (pin "32") (pinfunction "CTRL_MODE_32") (pintype "passive"))
      (node (ref "U3") (pin "7") (pinfunction "AGND_7") (pintype "power_in"))
      (node (ref "U4") (pin "2") (pinfunction "GND_2") (pintype "power_in"))
      (node (ref "U5") (pin "5") (pinfunction "VREFL_5") (pintype "bidirectional"))
      (node (ref "U5") (pin "6") (pinfunction "VSS_6") (pintype "bidirectional"))
      (node (ref "U6") (pin "31") (pinfunction "VSS_31") (pintype "bidirectional"))
      (node (ref "U6") (pin "4") (pinfunction "VSS_4") (pintype "bidirectional"))
      (node (ref "U6") (pin "47") (pinfunction "VSS_47") (pintype "bidirectional"))
      (node (ref "U7") (pin "1") (pinfunction "GND_1") (pintype "bidirectional"))
      (node (ref "U7") (pin "12") (pinfunction "GND1_12") (pintype "bidirectional"))
      (node (ref "U7") (pin "25") (pinfunction "GND2_25") (pintype "bidirectional"))
      (node (ref "U7") (pin "27") (pinfunction "GND3_27") (pintype "bidirectional"))
      (node (ref "U7") (pin "28") (pinfunction "GND4_28") (pintype "bidirectional"))
      (node (ref "U7") (pin "29") (pinfunction "GND5_29") (pintype "bidirectional"))
      (node (ref "U8") (pin "2") (pinfunction "GND_2") (pintype "bidirectional"))
      (node (ref "U8") (pin "PAD") (pinfunction "PAD_PAD") (pintype "bidirectional"))
    )
    (net (code "58") (name "Net-(J2-PadD+)") (class "Default")
      (node (ref "J2") (pin "D+") (pinfunction "D+_D+") (pintype "bidirectional"))
      (node (ref "R7") (pin "1") (pinfunction "1_1") (pintype "passive"))
    )
    (net (code "59") (name "Net-(J2-PadD-)") (class "Default")
      (node (ref "J2") (pin "D-") (pinfunction "D-_D-") (pintype "bidirectional"))
      (node (ref "R8") (pin "1") (pinfunction "1_1") (pintype "passive"))
    )
    (net (code "60") (name "Net-(LED1-PadC)") (class "Default")
      (node (ref "LED1") (pin "C") (pinfunction "C_C") (pintype "passive"))
      (node (ref "R1") (pin "2") (pinfunction "2_2") (pintype "passive"))
    )
    (net (code "61") (name "Net-(LED2-PadC)") (class "Default")
      (node (ref "LED2") (pin "C") (pinfunction "C_C") (pintype "passive"))
      (node (ref "R2") (pin "2") (pinfunction "2_2") (pintype "passive"))
    )
    (net (code "62") (name "Net-(LED3-PadC)") (class "Default")
      (node (ref "LED3") (pin "C") (pinfunction "C_C") (pintype "passive"))
      (node (ref "R3") (pin "2") (pinfunction "2_2") (pintype "passive"))
    )
    (net (code "63") (name "Net-(LED4-PadA)") (class "Default")
      (node (ref "LED4") (pin "A") (pinfunction "A_A") (pintype "passive"))
      (node (ref "R15") (pin "1") (pinfunction "1_1") (pintype "passive"))
    )
    (net (code "64") (name "Net-(LED5-PadC)") (class "Default")
      (node (ref "LED5") (pin "C") (pinfunction "C_C") (pintype "passive"))
      (node (ref "R17") (pin "1") (pinfunction "1_1") (pintype "passive"))
    )
    (net (code "65") (name "Net-(R18-Pad2)") (class "Default")
      (node (ref "R18") (pin "2") (pinfunction "2_2") (pintype "bidirectional"))
      (node (ref "SJ3") (pin "2") (pinfunction "2_2") (pintype "passive"))
    )
    (net (code "66") (name "Net-(U2-PROG)") (class "Default")
      (node (ref "R16") (pin "2") (pinfunction "2_2") (pintype "passive"))
      (node (ref "U2") (pin "5") (pinfunction "PROG_5") (pintype "input"))
    )
    (net (code "67") (name "Net-(U2-STAT)") (class "Default")
      (node (ref "R15") (pin "2") (pinfunction "2_2") (pintype "passive"))
      (node (ref "R17") (pin "2") (pinfunction "2_2") (pintype "passive"))
      (node (ref "U2") (pin "1") (pinfunction "STAT_1") (pintype "output"))
    )
    (net (code "68") (name "Net-(U2-VBAT)") (class "Default")
      (node (ref "C20") (pin "1") (pinfunction "1_1") (pintype "passive"))
      (node (ref "CN1") (pin "2") (pinfunction "2_2") (pintype "passive"))
      (node (ref "R18") (pin "1") (pinfunction "1_1") (pintype "bidirectional"))
      (node (ref "U2") (pin "3") (pinfunction "VBAT_3") (pintype "power_in"))
    )
    (net (code "69") (name "Net-(U3-I2S_DIN)") (class "Default")
      (node (ref "SJ1") (pin "1") (pinfunction "1_1") (pintype "passive"))
      (node (ref "U3") (pin "26") (pinfunction "I2S_DIN_26") (pintype "input"))
    )
    (net (code "70") (name "Net-(U3-I2S_DOUT)") (class "Default")
      (node (ref "SJ2") (pin "1") (pinfunction "1_1") (pintype "passive"))
      (node (ref "U3") (pin "25") (pinfunction "I2S_DOUT_25") (pintype "output"))
    )
    (net (code "71") (name "Net-(U3-LINEIN_L)") (class "Default")
      (node (ref "C18") (pin "1") (pinfunction "1_1") (pintype "passive"))
      (node (ref "U3") (pin "14") (pinfunction "LINEIN_L_14") (pintype "input"))
    )
    (net (code "72") (name "Net-(U3-LINEIN_R)") (class "Default")
      (node (ref "C13") (pin "1") (pinfunction "1_1") (pintype "passive"))
      (node (ref "U3") (pin "13") (pinfunction "LINEIN_R_13") (pintype "input"))
    )
    (net (code "73") (name "Net-(U3-LINEOUT_L)") (class "Default")
      (node (ref "C17") (pin "1") (pinfunction "1_1") (pintype "passive"))
      (node (ref "U3") (pin "12") (pinfunction "LINEOUT_L_12") (pintype "output"))
    )
    (net (code "74") (name "Net-(U3-LINEOUT_R)") (class "Default")
      (node (ref "C14") (pin "1") (pinfunction "1_1") (pintype "passive"))
      (node (ref "U3") (pin "11") (pinfunction "LINEOUT_R_11") (pintype "output"))
    )
    (net (code "75") (name "Net-(U3-MIC)") (class "Default")
      (node (ref "C15") (pin "1") (pinfunction "1_1") (pintype "passive"))
      (node (ref "U3") (pin "15") (pinfunction "MIC_15") (pintype "input"))
    )
    (net (code "76") (name "Net-(U3-MIC_BIAS)") (class "Default")
      (node (ref "C12") (pin "1") (pinfunction "1_1") (pintype "passive"))
      (node (ref "R13") (pin "2") (pinfunction "2_2") (pintype "passive"))
      (node (ref "U3") (pin "16") (pinfunction "MIC_BIAS_16") (pintype "passive"))
    )
    (net (code "77") (name "Net-(U3-VAG)") (class "Default")
      (node (ref "C16") (pin "1") (pinfunction "1_1") (pintype "passive"))
      (node (ref "U3") (pin "10") (pinfunction "VAG_10") (pintype "passive"))
    )
    (net (code "78") (name "Net-(U3-VDDA)") (class "Default")
      (node (ref "C21") (pin "1") (pinfunction "1_1") (pintype "passive"))
      (node (ref "R20") (pin "1") (pinfunction "1_1") (pintype "passive"))
      (node (ref "U3") (pin "5") (pinfunction "VDDA_5") (pintype "power_in"))
    )
    (net (code "79") (name "Net-(U3-VDDD)") (class "Default")
      (node (ref "U3") (pin "30") (pinfunction "VDDD_30") (pintype "power_in"))
      (node (ref "U4") (pin "5") (pinfunction "OUT_5") (pintype "output"))
    )
    (net (code "80") (name "Net-(U4-NR)") (class "Default")
      (node (ref "C22") (pin "2") (pinfunction "2_2") (pintype "passive"))
      (node (ref "U4") (pin "4") (pinfunction "NR_4") (pintype "passive"))
    )
    (net (code "81") (name "Net-(U5-PTA7)") (class "Default")
      (node (ref "U5") (pin "15") (pinfunction "PTA7_15") (pintype "bidirectional"))
      (node (ref "U6") (pin "25") (pinfunction "PTA3_25") (pintype "bidirectional"))
    )
    (net (code "82") (name "Net-(U5-PTB0)") (class "Default")
      (node (ref "U5") (pin "16") (pinfunction "PTB0_16") (pintype "bidirectional"))
      (node (ref "U6") (pin "22") (pinfunction "PTA0_22") (pintype "bidirectional"))
    )
    (net (code "83") (name "Net-(U5-PTB1)") (class "Default")
      (node (ref "U5") (pin "17") (pinfunction "PTB1_17") (pintype "bidirectional"))
      (node (ref "U6") (pin "24") (pinfunction "PTA2_24") (pintype "bidirectional"))
    )
    (net (code "84") (name "Net-(U6-PTA18)") (class "Default")
      (node (ref "C3") (pin "1") (pinfunction "1_1") (pintype "passive"))
      (node (ref "K1") (pin "1") (pinfunction "1_1") (pintype "passive"))
      (node (ref "U6") (pin "32") (pinfunction "PTA18_32") (pintype "bidirectional"))
    )
    (net (code "85") (name "Net-(U6-PTA19)") (class "Default")
      (node (ref "C4") (pin "1") (pinfunction "1_1") (pintype "passive"))
      (node (ref "K1") (pin "2") (pinfunction "2_2") (pintype "passive"))
      (node (ref "U6") (pin "33") (pinfunction "PTA19_33") (pintype "bidirectional"))
    )
    (net (code "86") (name "Net-(U6-USB0_DM)") (class "Default")
      (node (ref "R8") (pin "2") (pinfunction "2_2") (pintype "passive"))
      (node (ref "U6") (pin "6") (pinfunction "USB0_DM_6") (pintype "bidirectional"))
    )
    (net (code "87") (name "Net-(U6-USB0_DP)") (class "Default")
      (node (ref "R7") (pin "2") (pinfunction "2_2") (pintype "passive"))
      (node (ref "U6") (pin "5") (pinfunction "USB0_DP_5") (pintype "bidirectional"))
    )
    (net (code "88") (name "Net-(U6-VBAT)") (class "Default")
      (node (ref "C2") (pin "1") (pinfunction "1_1") (pintype "passive"))
      (node (ref "R5") (pin "3") (pinfunction "3_3") (pintype "bidirectional"))
      (node (ref "U6") (pin "21") (pinfunction "VBAT_21") (pintype "bidirectional"))
    )
    (net (code "89") (name "Net-(U6-VDDA)") (class "Default")
      (node (ref "C7") (pin "1") (pinfunction "1_1") (pintype "passive"))
      (node (ref "R11") (pin "1") (pinfunction "1_1") (pintype "passive"))
      (node (ref "R12") (pin "1") (pinfunction "1_1") (pintype "passive"))
      (node (ref "U6") (pin "13") (pinfunction "VDDA_13") (pintype "bidirectional"))
    )
    (net (code "90") (name "Net-(U6-VREFH)") (class "Default")
      (node (ref "C5") (pin "1") (pinfunction "1_1") (pintype "passive"))
      (node (ref "R11") (pin "2") (pinfunction "2_2") (pintype "passive"))
      (node (ref "U6") (pin "14") (pinfunction "VREFH_14") (pintype "bidirectional"))
    )
    (net (code "91") (name "Net-(U6-VREF_OUT)") (class "Default")
      (node (ref "C6") (pin "1") (pinfunction "1_1") (pintype "passive"))
      (node (ref "U6") (pin "17") (pinfunction "VREF_OUT_17") (pintype "bidirectional"))
    )
    (net (code "92") (name "Net-(U7-PIO2)") (class "Default")
      (node (ref "LED3") (pin "A") (pinfunction "A_A") (pintype "passive"))
      (node (ref "U7") (pin "19") (pinfunction "PIO2_19") (pintype "bidirectional"))
    )
    (net (code "93") (name "Net-(U7-PIO4)") (class "Default")
      (node (ref "JP1") (pin "1") (pinfunction "1_1") (pintype "passive"))
      (node (ref "R4") (pin "2") (pinfunction "2_2") (pintype "passive"))
      (node (ref "U7") (pin "22") (pinfunction "PIO4_22") (pintype "bidirectional"))
    )
    (net (code "94") (name "Net-(U7-PIO5)") (class "Default")
      (node (ref "LED2") (pin "A") (pinfunction "A_A") (pintype "passive"))
      (node (ref "U7") (pin "21") (pinfunction "PIO5_21") (pintype "bidirectional"))
    )
    (net (code "95") (name "VIN") (class "Default")
      (node (ref "C11") (pin "1") (pinfunction "1_1") (pintype "passive"))
      (node (ref "J5") (pin "10") (pinfunction "10_10") (pintype "passive"))
      (node (ref "R18") (pin "3") (pinfunction "3_3") (pintype "bidirectional"))
      (node (ref "U4") (pin "1") (pinfunction "IN_1") (pintype "input"))
      (node (ref "U4") (pin "3") (pinfunction "EN_3") (pintype "passive"))
      (node (ref "U8") (pin "1") (pinfunction "IN_1") (pintype "bidirectional"))
    )
    (net (code "96") (name "V_USB") (class "Default")
      (node (ref "C19") (pin "1") (pinfunction "1_1") (pintype "passive"))
      (node (ref "J2") (pin "VBUS") (pinfunction "VBUS_VBUS") (pintype "power_in"))
      (node (ref "LED5") (pin "A") (pinfunction "A_A") (pintype "passive"))
      (node (ref "SJ3") (pin "1") (pinfunction "1_1") (pintype "passive"))
      (node (ref "U2") (pin "4") (pinfunction "VDD_4") (pintype "power_in"))
    )
    (net (code "97") (name "unconnected-(J7-PadRING2)") (class "Default")
      (node (ref "J7") (pin "RING2") (pinfunction "RING2_RING2") (pintype "bidirectional"))
    )
    (net (code "98") (name "unconnected-(U1-NC-Pad1)") (class "Default")
      (node (ref "U1") (pin "1") (pinfunction "NC_1") (pintype "bidirectional"))
    )
    (net (code "99") (name "unconnected-(U1-PadCD1)") (class "Default")
      (node (ref "U1") (pin "CD1") (pinfunction "CD1_CD1") (pintype "bidirectional"))
    )
    (net (code "100") (name "unconnected-(U1-RSV-Pad8)") (class "Default")
      (node (ref "U1") (pin "8") (pinfunction "RSV_8") (pintype "bidirectional"))
    )
    (net (code "101") (name "unconnected-(U3-CPFLT-Pad18)") (class "Default")
      (node (ref "U3") (pin "18") (pinfunction "CPFLT_18") (pintype "passive"))
    )
    (net (code "102") (name "unconnected-(U3-NC-Pad28)") (class "Default")
      (node (ref "U3") (pin "28") (pinfunction "NC_28") (pintype "passive"))
    )
    (net (code "103") (name "unconnected-(U3-NC_2-Pad8)") (class "Default")
      (node (ref "U3") (pin "8") (pinfunction "NC_2_8") (pintype "passive"))
    )
    (net (code "104") (name "unconnected-(U3-NC_3-Pad9)") (class "Default")
      (node (ref "U3") (pin "9") (pinfunction "NC_3_9") (pintype "passive"))
    )
    (net (code "105") (name "unconnected-(U3-NC_4-Pad17)") (class "Default")
      (node (ref "U3") (pin "17") (pinfunction "NC_4_17") (pintype "passive"))
    )
    (net (code "106") (name "unconnected-(U3-NC_5-Pad19)") (class "Default")
      (node (ref "U3") (pin "19") (pinfunction "NC_5_19") (pintype "passive"))
    )
    (net (code "107") (name "unconnected-(U3-NC_6-Pad22)") (class "Default")
      (node (ref "U3") (pin "22") (pinfunction "NC_6_22") (pintype "passive"))
    )
    (net (code "108") (name "unconnected-(U5-PTA0-Pad30)") (class "Default")
      (node (ref "U5") (pin "30") (pinfunction "PTA0_30") (pintype "bidirectional"))
    )
    (net (code "109") (name "unconnected-(U5-PTA1-Pad31)") (class "Default")
      (node (ref "U5") (pin "31") (pinfunction "PTA1_31") (pintype "bidirectional"))
    )
    (net (code "110") (name "unconnected-(U5-PTA2-Pad32)") (class "Default")
      (node (ref "U5") (pin "32") (pinfunction "PTA2_32") (pintype "bidirectional"))
    )
    (net (code "111") (name "unconnected-(U5-PTA3-Pad7)") (class "Default")
      (node (ref "U5") (pin "7") (pinfunction "PTA3_7") (pintype "bidirectional"))
    )
    (net (code "112") (name "unconnected-(U5-PTA5-Pad9)") (class "Default")
      (node (ref "U5") (pin "9") (pinfunction "PTA5_9") (pintype "bidirectional"))
    )
    (net (code "113") (name "unconnected-(U5-PTB3-Pad23)") (class "Default")
      (node (ref "U5") (pin "23") (pinfunction "PTB3_23") (pintype "bidirectional"))
    )
    (net (code "114") (name "unconnected-(U5-PTB4-Pad24)") (class "Default")
      (node (ref "U5") (pin "24") (pinfunction "PTB4_24") (pintype "bidirectional"))
    )
    (net (code "115") (name "unconnected-(U6-ADC0_DM0-Pad10)") (class "Default")
      (node (ref "U6") (pin "10") (pinfunction "ADC0_DM0_10") (pintype "bidirectional"))
    )
    (net (code "116") (name "unconnected-(U6-ADC0_DP0-Pad9)") (class "Default")
      (node (ref "U6") (pin "9") (pinfunction "ADC0_DP0_9") (pintype "bidirectional"))
    )
    (net (code "117") (name "unconnected-(U6-EXTAL32-Pad20)") (class "Default")
      (node (ref "U6") (pin "20") (pinfunction "EXTAL32_20") (pintype "bidirectional"))
    )
    (net (code "118") (name "unconnected-(U6-VREGIN-Pad8)") (class "Default")
      (node (ref "U6") (pin "8") (pinfunction "VREGIN_8") (pintype "bidirectional"))
    )
    (net (code "119") (name "unconnected-(U6-XTAL32-Pad19)") (class "Default")
      (node (ref "U6") (pin "19") (pinfunction "XTAL32_19") (pintype "bidirectional"))
    )
    (net (code "120") (name "unconnected-(U7-AIO1-Pad35)") (class "Default")
      (node (ref "U7") (pin "35") (pinfunction "AIO1_35") (pintype "bidirectional"))
    )
    (net (code "121") (name "unconnected-(U7-AIO2-Pad30)") (class "Default")
      (node (ref "U7") (pin "30") (pinfunction "AIO2_30") (pintype "bidirectional"))
    )
    (net (code "122") (name "unconnected-(U7-NC-Pad26)") (class "Default")
      (node (ref "U7") (pin "26") (pinfunction "NC_26") (pintype "bidirectional"))
    )
    (net (code "123") (name "unconnected-(U7-PCMCLK-Pad7)") (class "Default")
      (node (ref "U7") (pin "7") (pinfunction "PCMCLK_7") (pintype "bidirectional"))
    )
    (net (code "124") (name "unconnected-(U7-PCMIN-Pad9)") (class "Default")
      (node (ref "U7") (pin "9") (pinfunction "PCMIN_9") (pintype "bidirectional"))
    )
    (net (code "125") (name "unconnected-(U7-PCMOUT-Pad10)") (class "Default")
      (node (ref "U7") (pin "10") (pinfunction "PCMOUT_10") (pintype "bidirectional"))
    )
    (net (code "126") (name "unconnected-(U7-PCMSYNC-Pad8)") (class "Default")
      (node (ref "U7") (pin "8") (pinfunction "PCMSYNC_8") (pintype "bidirectional"))
    )
    (net (code "127") (name "unconnected-(U7-PIO3-Pad20)") (class "Default")
      (node (ref "U7") (pin "20") (pinfunction "PIO3_20") (pintype "bidirectional"))
    )
    (net (code "128") (name "unconnected-(U7-PIO6-Pad3)") (class "Default")
      (node (ref "U7") (pin "3") (pinfunction "PIO6_3") (pintype "bidirectional"))
    )
    (net (code "129") (name "unconnected-(U7-PIO7-Pad4)") (class "Default")
      (node (ref "U7") (pin "4") (pinfunction "PIO7_4") (pintype "bidirectional"))
    )
    (net (code "130") (name "unconnected-(U7-PIO8-Pad34)") (class "Default")
      (node (ref "U7") (pin "34") (pinfunction "PIO8_34") (pintype "bidirectional"))
    )
    (net (code "131") (name "unconnected-(U7-PIO9-Pad33)") (class "Default")
      (node (ref "U7") (pin "33") (pinfunction "PIO9_33") (pintype "bidirectional"))
    )
    (net (code "132") (name "unconnected-(U7-PIO10-Pad32)") (class "Default")
      (node (ref "U7") (pin "32") (pinfunction "PIO10_32") (pintype "bidirectional"))
    )
    (net (code "133") (name "unconnected-(U7-PIO11-Pad31)") (class "Default")
      (node (ref "U7") (pin "31") (pinfunction "PIO11_31") (pintype "bidirectional"))
    )
    (net (code "134") (name "unconnected-(U7-RESET-Pad5)") (class "Default")
      (node (ref "U7") (pin "5") (pinfunction "RESET_5") (pintype "bidirectional"))
    )
    (net (code "135") (name "unconnected-(U7-SPICLK-Pad6)") (class "Default")
      (node (ref "U7") (pin "6") (pinfunction "SPICLK_6") (pintype "bidirectional"))
    )
    (net (code "136") (name "unconnected-(U7-SPICSB-Pad23)") (class "Default")
      (node (ref "U7") (pin "23") (pinfunction "SPICSB_23") (pintype "bidirectional"))
    )
    (net (code "137") (name "unconnected-(U7-SPIMISO-Pad24)") (class "Default")
      (node (ref "U7") (pin "24") (pinfunction "SPIMISO_24") (pintype "bidirectional"))
    )
    (net (code "138") (name "unconnected-(U7-SPIMOSI-Pad2)") (class "Default")
      (node (ref "U7") (pin "2") (pinfunction "SPIMOSI_2") (pintype "bidirectional"))
    )
    (net (code "139") (name "unconnected-(U7-USBD+-Pad17)") (class "Default")
      (node (ref "U7") (pin "17") (pinfunction "USBD+_17") (pintype "bidirectional"))
    )
    (net (code "140") (name "unconnected-(U7-USBD--Pad18)") (class "Default")
      (node (ref "U7") (pin "18") (pinfunction "USBD-_18") (pintype "bidirectional"))
    )
  )
)
